# Schematic.net
KiCad netlist of a schematic drawn in Altium Designer
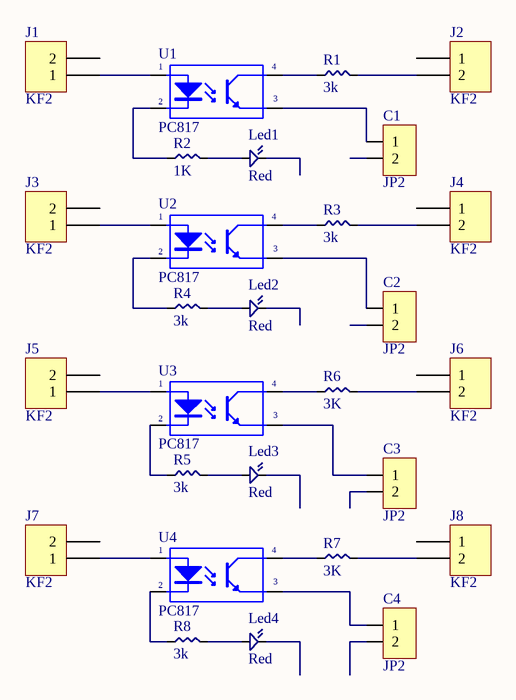
[diagram p0: Schematic.SchDoc]

(export (version "E")
  (design (tool "Eeschema 10.0.6"))
  (components
    (comp (ref "C1")
      (value "JP2")
      (footprint "JP2-D1T")
      (description "WR-PHD 2.54 mm Angled Socket Header")
      (fields
        (field (name "MANUFACTURER") "Würth Elektronik eiSos GmbH")
        (field (name "PARTNO") "613002143121")
        (field (name "CREATED BY") "Karrer Zheng")
      )
      (libsource (lib "LIBRARY") (part "JP2"))
    )
    (comp (ref "C2")
      (value "JP2")
      (footprint "JP2-D1T")
      (description "WR-PHD 2.54 mm Angled Socket Header")
      (fields
        (field (name "MANUFACTURER") "Würth Elektronik eiSos GmbH")
        (field (name "PARTNO") "613002143121")
        (field (name "CREATED BY") "Karrer Zheng")
      )
      (libsource (lib "LIBRARY") (part "JP2"))
    )
    (comp (ref "C3")
      (value "JP2")
      (footprint "JP2-D1T")
      (description "WR-PHD 2.54 mm Angled Socket Header")
      (fields
        (field (name "MANUFACTURER") "Würth Elektronik eiSos GmbH")
        (field (name "PARTNO") "613002143121")
        (field (name "CREATED BY") "Karrer Zheng")
      )
      (libsource (lib "LIBRARY") (part "JP2"))
    )
    (comp (ref "C4")
      (value "JP2")
      (footprint "JP2-D1T")
      (description "WR-PHD 2.54 mm Angled Socket Header")
      (fields
        (field (name "MANUFACTURER") "Würth Elektronik eiSos GmbH")
        (field (name "PARTNO") "613002143121")
        (field (name "CREATED BY") "Karrer Zheng")
      )
      (libsource (lib "LIBRARY") (part "JP2"))
    )
    (comp (ref "J1")
      (value "KF2")
      (footprint "KF2-3.5")
      (fields
        (field (name "MANUFACTURER") "Würth Elektronik eiSos GmbH")
        (field (name "PARTNO") "691103110002")
        (field (name "CREATED BY") "Karrer Zheng")
      )
      (libsource (lib "") (part "KF2_1"))
    )
    (comp (ref "J2")
      (value "KF2")
      (footprint "KF2-3.5")
      (fields
        (field (name "MANUFACTURER") "Würth Elektronik eiSos GmbH")
        (field (name "PARTNO") "691103110002")
        (field (name "CREATED BY") "Karrer Zheng")
      )
      (libsource (lib "LIBRARY") (part "KF2"))
    )
    (comp (ref "J3")
      (value "KF2")
      (footprint "KF2-3.5")
      (fields
        (field (name "MANUFACTURER") "Würth Elektronik eiSos GmbH")
        (field (name "PARTNO") "691103110002")
        (field (name "CREATED BY") "Karrer Zheng")
      )
      (libsource (lib "") (part "KF2_1"))
    )
    (comp (ref "J4")
      (value "KF2")
      (footprint "KF2-3.5")
      (fields
        (field (name "MANUFACTURER") "Würth Elektronik eiSos GmbH")
        (field (name "PARTNO") "691103110002")
        (field (name "CREATED BY") "Karrer Zheng")
      )
      (libsource (lib "LIBRARY") (part "KF2"))
    )
    (comp (ref "J5")
      (value "KF2")
      (footprint "KF2-3.5")
      (fields
        (field (name "MANUFACTURER") "Würth Elektronik eiSos GmbH")
        (field (name "PARTNO") "691103110002")
        (field (name "CREATED BY") "Karrer Zheng")
      )
      (libsource (lib "") (part "KF2_1"))
    )
    (comp (ref "J6")
      (value "KF2")
      (footprint "KF2-3.5")
      (fields
        (field (name "MANUFACTURER") "Würth Elektronik eiSos GmbH")
        (field (name "PARTNO") "691103110002")
        (field (name "CREATED BY") "Karrer Zheng")
      )
      (libsource (lib "LIBRARY") (part "KF2"))
    )
    (comp (ref "J7")
      (value "KF2")
      (footprint "KF2-3.5")
      (fields
        (field (name "MANUFACTURER") "Würth Elektronik eiSos GmbH")
        (field (name "PARTNO") "691103110002")
        (field (name "CREATED BY") "Karrer Zheng")
      )
      (libsource (lib "") (part "KF2_1"))
    )
    (comp (ref "J8")
      (value "KF2")
      (footprint "KF2-3.5")
      (fields
        (field (name "MANUFACTURER") "Würth Elektronik eiSos GmbH")
        (field (name "PARTNO") "691103110002")
        (field (name "CREATED BY") "Karrer Zheng")
      )
      (libsource (lib "LIBRARY") (part "KF2"))
    )
    (comp (ref "Led1")
      (value "Red")
      (footprint "LED 0603 SMD")
      (libsource (lib "library") (part "0603 SMD LED"))
    )
    (comp (ref "Led2")
      (value "Red")
      (footprint "LED 0603 SMD")
      (libsource (lib "library") (part "0603 SMD LED"))
    )
    (comp (ref "Led3")
      (value "Red")
      (footprint "LED 0603 SMD")
      (libsource (lib "library") (part "0603 SMD LED"))
    )
    (comp (ref "Led4")
      (value "Red")
      (footprint "LED 0603 SMD")
      (libsource (lib "library") (part "0603 SMD LED"))
    )
    (comp (ref "R1") (value "3k") (footprint "SMD 0603 Res") (libsource (lib "library") (part "0603 Res")))
    (comp (ref "R2") (value "1K") (footprint "SMD 0603 Res") (libsource (lib "library") (part "0603 Res")))
    (comp (ref "R3") (value "3k") (footprint "SMD 0603 Res") (libsource (lib "library") (part "0603 Res")))
    (comp (ref "R4") (value "3k") (footprint "SMD 0603 Res") (libsource (lib "library") (part "0603 Res")))
    (comp (ref "R5") (value "3k") (footprint "SMD 0603 Res") (libsource (lib "library") (part "0603 Res")))
    (comp (ref "R6") (value "3K") (footprint "SMD 0603 Res") (libsource (lib "library") (part "0603 Res")))
    (comp (ref "R7") (value "3K") (footprint "SMD 0603 Res") (libsource (lib "library") (part "0603 Res")))
    (comp (ref "R8") (value "3k") (footprint "SMD 0603 Res") (libsource (lib "library") (part "0603 Res")))
    (comp (ref "U1")
      (value "PC817")
      (footprint "DIP4")
      (description "Single Opto")
      (libsource (lib "LIBRARY") (part "PC817"))
    )
    (comp (ref "U2")
      (value "PC817")
      (footprint "DIP4")
      (description "Single Opto")
      (libsource (lib "LIBRARY") (part "PC817"))
    )
    (comp (ref "U3")
      (value "PC817")
      (footprint "DIP4")
      (description "Single Opto")
      (libsource (lib "LIBRARY") (part "PC817"))
    )
    (comp (ref "U4")
      (value "PC817")
      (footprint "DIP4")
      (description "Single Opto")
      (libsource (lib "LIBRARY") (part "PC817"))
    )
  )
  (nets
    (net (code "1") (name "Net-(J2-Pad2)") (class "Default")
      (node (ref "J2") (pin "2") (pinfunction "2_2") (pintype "passive"))
      (node (ref "R1") (pin "2") (pinfunction "2_2") (pintype "passive"))
    )
    (net (code "2") (name "Net-(J4-Pad2)") (class "Default")
      (node (ref "J4") (pin "2") (pinfunction "2_2") (pintype "passive"))
      (node (ref "R3") (pin "2") (pinfunction "2_2") (pintype "passive"))
    )
    (net (code "3") (name "Net-(J6-Pad2)") (class "Default")
      (node (ref "J6") (pin "2") (pinfunction "2_2") (pintype "passive"))
      (node (ref "R6") (pin "2") (pinfunction "2_2") (pintype "passive"))
    )
    (net (code "4") (name "Net-(J8-Pad2)") (class "Default")
      (node (ref "J8") (pin "2") (pinfunction "2_2") (pintype "passive"))
      (node (ref "R7") (pin "2") (pinfunction "2_2") (pintype "passive"))
    )
    (net (code "5") (name "Net-(Led1-Pad1)") (class "Default")
      (node (ref "Led1") (pin "1") (pinfunction "1_1") (pintype "passive"))
      (node (ref "R2") (pin "2") (pinfunction "2_2") (pintype "passive"))
    )
    (net (code "6") (name "Net-(Led2-Pad1)") (class "Default")
      (node (ref "Led2") (pin "1") (pinfunction "1_1") (pintype "passive"))
      (node (ref "R4") (pin "2") (pinfunction "2_2") (pintype "passive"))
    )
    (net (code "7") (name "Net-(Led3-Pad1)") (class "Default")
      (node (ref "Led3") (pin "1") (pinfunction "1_1") (pintype "passive"))
      (node (ref "R5") (pin "2") (pinfunction "2_2") (pintype "passive"))
    )
    (net (code "8") (name "Net-(Led4-Pad1)") (class "Default")
      (node (ref "Led4") (pin "1") (pinfunction "1_1") (pintype "passive"))
      (node (ref "R8") (pin "2") (pinfunction "2_2") (pintype "passive"))
    )
    (net (code "9") (name "Net-(U1-A)") (class "Default")
      (node (ref "J1") (pin "1") (pinfunction "1_1") (pintype "passive"))
      (node (ref "U1") (pin "1") (pinfunction "A_1") (pintype "passive"))
    )
    (net (code "10") (name "Net-(U1-C)") (class "Default")
      (node (ref "R1") (pin "1") (pinfunction "1_1") (pintype "passive"))
      (node (ref "U1") (pin "4") (pinfunction "C_4") (pintype "passive"))
    )
    (net (code "11") (name "Net-(U1-E)") (class "Default")
      (node (ref "C1") (pin "1") (pinfunction "1_1") (pintype "passive"))
      (node (ref "U1") (pin "3") (pinfunction "E_3") (pintype "passive"))
    )
    (net (code "12") (name "Net-(U1-K)") (class "Default")
      (node (ref "R2") (pin "1") (pinfunction "1_1") (pintype "passive"))
      (node (ref "U1") (pin "2") (pinfunction "K_2") (pintype "passive"))
    )
    (net (code "13") (name "Net-(U2-A)") (class "Default")
      (node (ref "J3") (pin "1") (pinfunction "1_1") (pintype "passive"))
      (node (ref "U2") (pin "1") (pinfunction "A_1") (pintype "passive"))
    )
    (net (code "14") (name "Net-(U2-C)") (class "Default")
      (node (ref "R3") (pin "1") (pinfunction "1_1") (pintype "passive"))
      (node (ref "U2") (pin "4") (pinfunction "C_4") (pintype "passive"))
    )
    (net (code "15") (name "Net-(U2-E)") (class "Default")
      (node (ref "C2") (pin "1") (pinfunction "1_1") (pintype "passive"))
      (node (ref "U2") (pin "3") (pinfunction "E_3") (pintype "passive"))
    )
    (net (code "16") (name "Net-(U2-K)") (class "Default")
      (node (ref "R4") (pin "1") (pinfunction "1_1") (pintype "passive"))
      (node (ref "U2") (pin "2") (pinfunction "K_2") (pintype "passive"))
    )
    (net (code "17") (name "Net-(U3-A)") (class "Default")
      (node (ref "J5") (pin "1") (pinfunction "1_1") (pintype "passive"))
      (node (ref "U3") (pin "1") (pinfunction "A_1") (pintype "passive"))
    )
    (net (code "18") (name "Net-(U3-C)") (class "Default")
      (node (ref "R6") (pin "1") (pinfunction "1_1") (pintype "passive"))
      (node (ref "U3") (pin "4") (pinfunction "C_4") (pintype "passive"))
    )
    (net (code "19") (name "Net-(U3-E)") (class "Default")
      (node (ref "C3") (pin "1") (pinfunction "1_1") (pintype "passive"))
      (node (ref "U3") (pin "3") (pinfunction "E_3") (pintype "passive"))
    )
    (net (code "20") (name "Net-(U3-K)") (class "Default")
      (node (ref "R5") (pin "1") (pinfunction "1_1") (pintype "passive"))
      (node (ref "U3") (pin "2") (pinfunction "K_2") (pintype "passive"))
    )
    (net (code "21") (name "Net-(U4-A)") (class "Default")
      (node (ref "J7") (pin "1") (pinfunction "1_1") (pintype "passive"))
      (node (ref "U4") (pin "1") (pinfunction "A_1") (pintype "passive"))
    )
    (net (code "22") (name "Net-(U4-C)") (class "Default")
      (node (ref "R7") (pin "1") (pinfunction "1_1") (pintype "passive"))
      (node (ref "U4") (pin "4") (pinfunction "C_4") (pintype "passive"))
    )
    (net (code "23") (name "Net-(U4-E)") (class "Default")
      (node (ref "C4") (pin "1") (pinfunction "1_1") (pintype "passive"))
      (node (ref "U4") (pin "3") (pinfunction "E_3") (pintype "passive"))
    )
    (net (code "24") (name "Net-(U4-K)") (class "Default")
      (node (ref "R8") (pin "1") (pinfunction "1_1") (pintype "passive"))
      (node (ref "U4") (pin "2") (pinfunction "K_2") (pintype "passive"))
    )
    (net (code "25") (name "unconnected-(C1-Pad2)") (class "Default")
      (node (ref "C1") (pin "2") (pinfunction "2_2") (pintype "passive"))
    )
    (net (code "26") (name "unconnected-(C2-Pad2)") (class "Default")
      (node (ref "C2") (pin "2") (pinfunction "2_2") (pintype "passive"))
    )
    (net (code "27") (name "unconnected-(C3-Pad2)") (class "Default")
      (node (ref "C3") (pin "2") (pinfunction "2_2") (pintype "passive"))
    )
    (net (code "28") (name "unconnected-(C4-Pad2)") (class "Default")
      (node (ref "C4") (pin "2") (pinfunction "2_2") (pintype "passive"))
    )
    (net (code "29") (name "unconnected-(J1-Pad2)") (class "Default")
      (node (ref "J1") (pin "2") (pinfunction "2_2") (pintype "passive"))
    )
    (net (code "30") (name "unconnected-(J2-Pad1)") (class "Default")
      (node (ref "J2") (pin "1") (pinfunction "1_1") (pintype "passive"))
    )
    (net (code "31") (name "unconnected-(J3-Pad2)") (class "Default")
      (node (ref "J3") (pin "2") (pinfunction "2_2") (pintype "passive"))
    )
    (net (code "32") (name "unconnected-(J4-Pad1)") (class "Default")
      (node (ref "J4") (pin "1") (pinfunction "1_1") (pintype "passive"))
    )
    (net (code "33") (name "unconnected-(J5-Pad2)") (class "Default")
      (node (ref "J5") (pin "2") (pinfunction "2_2") (pintype "passive"))
    )
    (net (code "34") (name "unconnected-(J6-Pad1)") (class "Default")
      (node (ref "J6") (pin "1") (pinfunction "1_1") (pintype "passive"))
    )
    (net (code "35") (name "unconnected-(J7-Pad2)") (class "Default")
      (node (ref "J7") (pin "2") (pinfunction "2_2") (pintype "passive"))
    )
    (net (code "36") (name "unconnected-(J8-Pad1)") (class "Default")
      (node (ref "J8") (pin "1") (pinfunction "1_1") (pintype "passive"))
    )
    (net (code "37") (name "unconnected-(Led1-Pad2)") (class "Default")
      (node (ref "Led1") (pin "2") (pinfunction "2_2") (pintype "passive"))
    )
    (net (code "38") (name "unconnected-(Led2-Pad2)") (class "Default")
      (node (ref "Led2") (pin "2") (pinfunction "2_2") (pintype "passive"))
    )
    (net (code "39") (name "unconnected-(Led3-Pad2)") (class "Default")
      (node (ref "Led3") (pin "2") (pinfunction "2_2") (pintype "passive"))
    )
    (net (code "40") (name "unconnected-(Led4-Pad2)") (class "Default")
      (node (ref "Led4") (pin "2") (pinfunction "2_2") (pintype "passive"))
    )
  )
)
